# UpDown.net
KiCad netlist of a schematic drawn in EAGLE
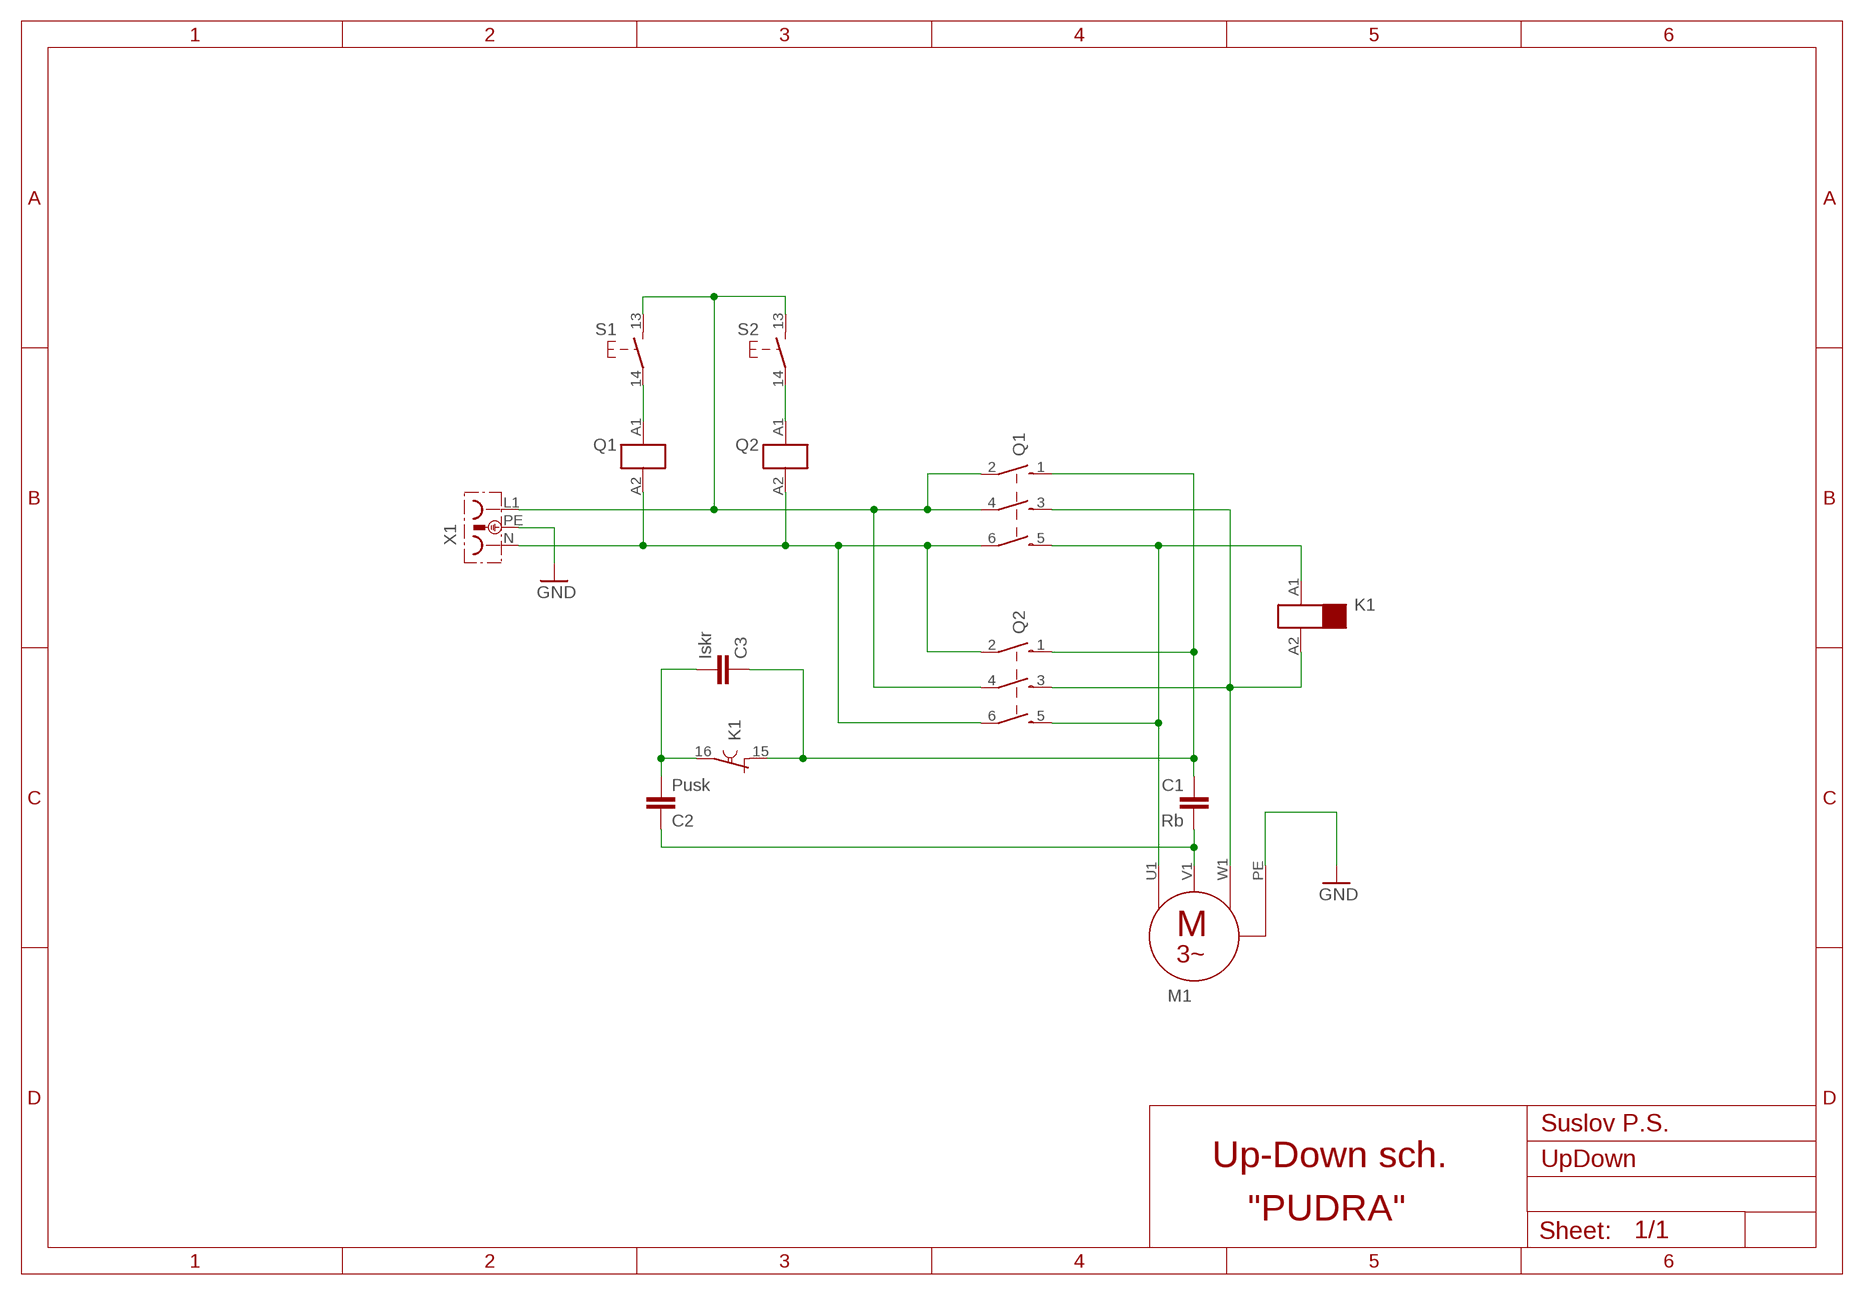
[diagram p0: schematic, sheet 1]

(export (version "E")
  (design (tool "Eeschema 10.0.6"))
  (components
    (comp (ref "C1")
      (value "Rb")
      (footprint "eagle-import:C025-024X044")
      (libsource (lib "eagle-import") (part "C-EU025-024X044"))
    )
    (comp (ref "C2")
      (value "Pusk")
      (footprint "eagle-import:C025-024X044")
      (libsource (lib "eagle-import") (part "C-EU025-024X044"))
    )
    (comp (ref "C3")
      (value "Iskr")
      (footprint "eagle-import:C025-024X044")
      (libsource (lib "eagle-import") (part "C-EU025-024X044"))
    )
    (comp (ref "K1")
      (value "HILFSSCHUETZ_SCHLIESST_VERZOEGERT_15-16")
      (footprint "eagle-import:HILFSSCHUETZ_SCHLIESST_VERZOEGERT_15-16")
      (libsource (lib "eagle-import") (part "HILFSSCHUETZ_SCHLIESST_VERZOEGERT_15-16"))
    )
    (comp (ref "M1")
      (value "MOTOR_3-POL_PE")
      (footprint "eagle-import:MOTOR_3-POL_PE")
      (libsource (lib "eagle-import") (part "MOTOR_3-POL_PE"))
    )
    (comp (ref "Q1")
      (value "HAUPTSCHUETZ_3-POL")
      (footprint "eagle-import:HAUPTSCHUETZ_3-POL")
      (libsource (lib "eagle-import") (part "HAUPTSCHUETZ_3-POL"))
    )
    (comp (ref "Q2")
      (value "HAUPTSCHUETZ_3-POL")
      (footprint "eagle-import:HAUPTSCHUETZ_3-POL")
      (libsource (lib "eagle-import") (part "HAUPTSCHUETZ_3-POL"))
    )
    (comp (ref "S1")
      (value "TASTER_SCHLIESSER")
      (footprint "eagle-import:EINTASTER")
      (libsource (lib "eagle-import") (part "TASTER_SCHLIESSER"))
    )
    (comp (ref "S2")
      (value "TASTER_SCHLIESSER")
      (footprint "eagle-import:EINTASTER")
      (libsource (lib "eagle-import") (part "TASTER_SCHLIESSER"))
    )
    (comp (ref "X1")
      (value "~220v")
      (footprint "eagle-import:STECKDOSE")
      (libsource (lib "eagle-import") (part "STECKDOSE"))
    )
  )
  (nets
    (net (code "1") (name "GND") (class "Default")
      (node (ref "M1") (pin "PE") (pinfunction "PE_PE") (pintype "passive"))
      (node (ref "X1") (pin "PE") (pinfunction "PE_PE") (pintype "passive"))
    )
    (net (code "2") (name "Net-(C1-Pad2)") (class "Default")
      (node (ref "C1") (pin "2") (pinfunction "2_2") (pintype "passive"))
      (node (ref "C2") (pin "1") (pinfunction "1_1") (pintype "passive"))
      (node (ref "M1") (pin "V1") (pinfunction "V1_V1") (pintype "passive"))
    )
    (net (code "3") (name "Net-(K1-PadA1)") (class "Default")
      (node (ref "K1") (pin "A1") (pinfunction "A1_A1") (pintype "passive"))
      (node (ref "M1") (pin "U1") (pinfunction "U1_U1") (pintype "passive"))
      (node (ref "Q1") (pin "5") (pinfunction "5_5") (pintype "passive"))
      (node (ref "Q2") (pin "5") (pinfunction "5_5") (pintype "passive"))
    )
    (net (code "4") (name "Net-(K1-PadA2)") (class "Default")
      (node (ref "K1") (pin "A2") (pinfunction "A2_A2") (pintype "passive"))
      (node (ref "M1") (pin "W1") (pinfunction "W1_W1") (pintype "passive"))
      (node (ref "Q1") (pin "3") (pinfunction "3_3") (pintype "passive"))
      (node (ref "Q2") (pin "3") (pinfunction "3_3") (pintype "passive"))
    )
    (net (code "5") (name "Net-(K1B-5)") (class "Default")
      (node (ref "C1") (pin "1") (pinfunction "1_1") (pintype "passive"))
      (node (ref "C3") (pin "1") (pinfunction "1_1") (pintype "passive"))
      (node (ref "K1") (pin "15") (pinfunction "5_15") (pintype "passive"))
      (node (ref "Q1") (pin "1") (pinfunction "1_1") (pintype "passive"))
      (node (ref "Q2") (pin "1") (pinfunction "1_1") (pintype "passive"))
    )
    (net (code "6") (name "Net-(K1B-6)") (class "Default")
      (node (ref "C2") (pin "2") (pinfunction "2_2") (pintype "passive"))
      (node (ref "C3") (pin "2") (pinfunction "2_2") (pintype "passive"))
      (node (ref "K1") (pin "16") (pinfunction "6_16") (pintype "passive"))
    )
    (net (code "7") (name "Net-(Q1-Pad2)") (class "Default")
      (node (ref "Q1") (pin "2") (pinfunction "2_2") (pintype "passive"))
      (node (ref "Q1") (pin "4") (pinfunction "4_4") (pintype "passive"))
      (node (ref "Q2") (pin "4") (pinfunction "4_4") (pintype "passive"))
      (node (ref "S1") (pin "13") (pinfunction "13_13") (pintype "passive"))
      (node (ref "S2") (pin "13") (pinfunction "13_13") (pintype "passive"))
      (node (ref "X1") (pin "L1") (pinfunction "L1_L1") (pintype "passive"))
    )
    (net (code "8") (name "Net-(Q1-Pad6)") (class "Default")
      (node (ref "Q1") (pin "6") (pinfunction "6_6") (pintype "passive"))
      (node (ref "Q1") (pin "A2") (pinfunction "A2_A2") (pintype "input"))
      (node (ref "Q2") (pin "2") (pinfunction "2_2") (pintype "passive"))
      (node (ref "Q2") (pin "6") (pinfunction "6_6") (pintype "passive"))
      (node (ref "Q2") (pin "A2") (pinfunction "A2_A2") (pintype "input"))
      (node (ref "X1") (pin "N") (pinfunction "N_N") (pintype "passive"))
    )
    (net (code "9") (name "Net-(Q1-PadA1)") (class "Default")
      (node (ref "Q1") (pin "A1") (pinfunction "A1_A1") (pintype "input"))
      (node (ref "S1") (pin "14") (pinfunction "14_14") (pintype "passive"))
    )
    (net (code "10") (name "Net-(Q2-PadA1)") (class "Default")
      (node (ref "Q2") (pin "A1") (pinfunction "A1_A1") (pintype "input"))
      (node (ref "S2") (pin "14") (pinfunction "14_14") (pintype "passive"))
    )
  )
)
